# conn_board_v1.net
KiCad netlist of a schematic drawn in EAGLE
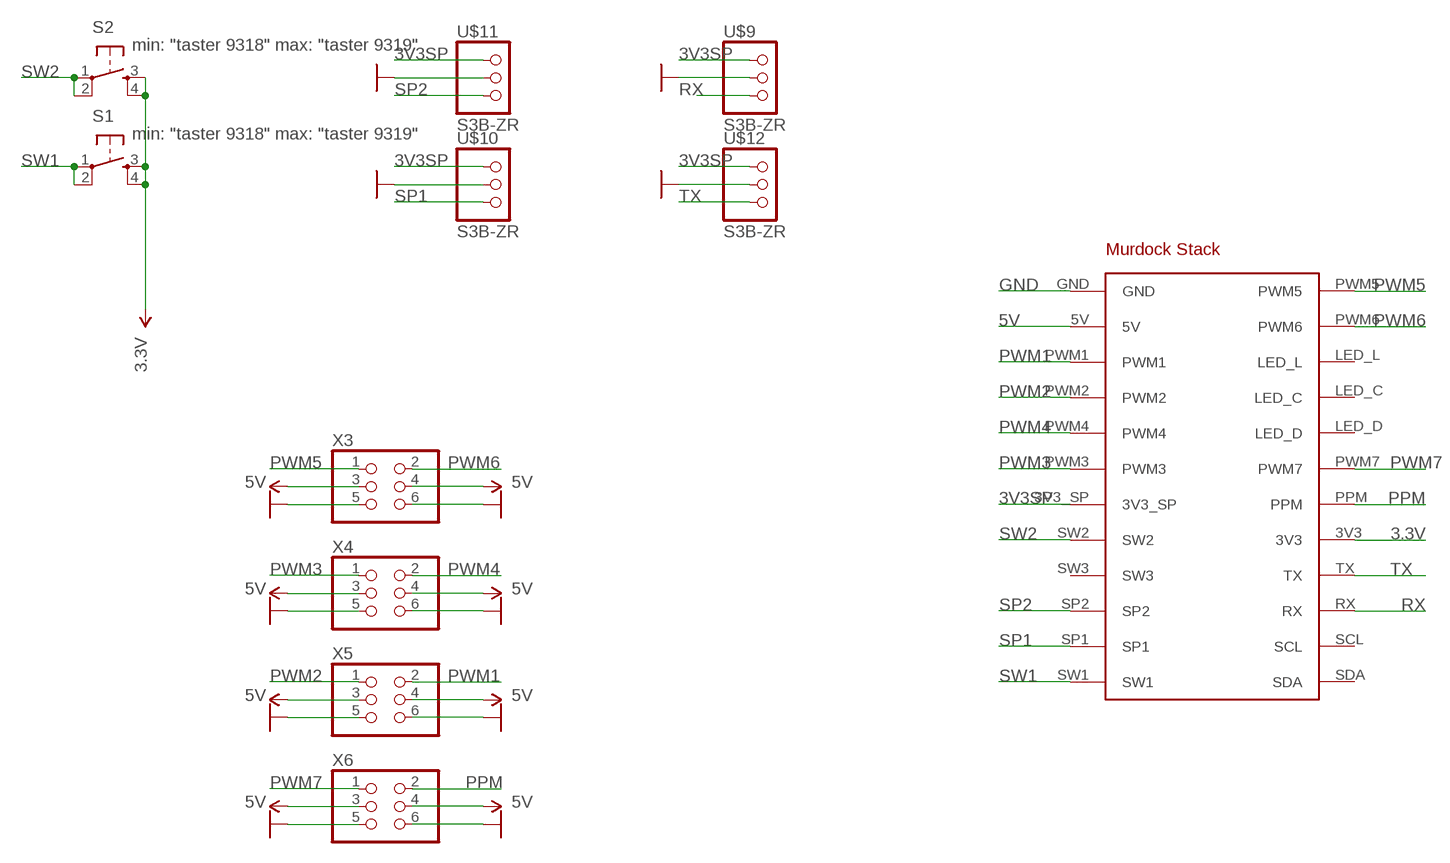
[diagram p0: schematic, sheet 1]

(export (version "E")
  (design (tool "Eeschema 10.0.6"))
  (components
    (comp (ref "S1")
      (value "min: \"taster 9318\" max: \"taster 9319\"")
      (footprint "eagle-import:LSH")
      (libsource (lib "eagle-import") (part "LSH"))
    )
    (comp (ref "S2")
      (value "min: \"taster 9318\" max: \"taster 9319\"")
      (footprint "eagle-import:LSH")
      (libsource (lib "eagle-import") (part "LSH"))
    )
    (comp (ref "U$9")
      (value "S3B-ZR")
      (footprint "eagle-import:S3B-ZR")
      (libsource (lib "eagle-import") (part "S3B-ZR"))
    )
    (comp (ref "U$10")
      (value "S3B-ZR")
      (footprint "eagle-import:S3B-ZR")
      (libsource (lib "eagle-import") (part "S3B-ZR"))
    )
    (comp (ref "U$11")
      (value "S3B-ZR")
      (footprint "eagle-import:S3B-ZR")
      (libsource (lib "eagle-import") (part "S3B-ZR"))
    )
    (comp (ref "U$12")
      (value "S3B-ZR")
      (footprint "eagle-import:S3B-ZR")
      (libsource (lib "eagle-import") (part "S3B-ZR"))
    )
    (comp (ref "X3")
      (value "PINHD-2X3/90")
      (footprint "eagle-import:2X03_90")
      (libsource (lib "eagle-import") (part "PINHD-2X3/90"))
    )
    (comp (ref "X4")
      (value "PINHD-2X3/90")
      (footprint "eagle-import:2X03_90")
      (libsource (lib "eagle-import") (part "PINHD-2X3/90"))
    )
    (comp (ref "X5")
      (value "PINHD-2X3/90")
      (footprint "eagle-import:2X03_90")
      (libsource (lib "eagle-import") (part "PINHD-2X3/90"))
    )
    (comp (ref "X6")
      (value "PINHD-2X3/90")
      (footprint "eagle-import:2X03_90")
      (libsource (lib "eagle-import") (part "PINHD-2X3/90"))
    )
    (comp (ref "X7")
      (value "MURDOCK_STACK")
      (footprint "eagle-import:MURDOCK_STACK")
      (libsource (lib "eagle-import") (part "MURDOCK_STACK"))
    )
  )
  (nets
    (net (code "1") (name "/3V3SP") (class "Default")
      (node (ref "U$10") (pin "1") (pinfunction "1_1") (pintype "bidirectional"))
      (node (ref "U$11") (pin "1") (pinfunction "1_1") (pintype "bidirectional"))
      (node (ref "U$12") (pin "1") (pinfunction "1_1") (pintype "bidirectional"))
      (node (ref "U$9") (pin "1") (pinfunction "1_1") (pintype "bidirectional"))
      (node (ref "X7") (pin "3V3_SP") (pinfunction "3V3_SP_3V3_SP") (pintype "bidirectional"))
    )
    (net (code "2") (name "/PPM") (class "Default")
      (node (ref "X6") (pin "2") (pinfunction "2_2") (pintype "passive"))
      (node (ref "X7") (pin "PPM") (pinfunction "PPM_PPM") (pintype "bidirectional"))
    )
    (net (code "3") (name "/PWM1") (class "Default")
      (node (ref "X5") (pin "2") (pinfunction "2_2") (pintype "passive"))
      (node (ref "X7") (pin "PWM1") (pinfunction "PWM1_PWM1") (pintype "bidirectional"))
    )
    (net (code "4") (name "/PWM2") (class "Default")
      (node (ref "X5") (pin "1") (pinfunction "1_1") (pintype "passive"))
      (node (ref "X7") (pin "PWM2") (pinfunction "PWM2_PWM2") (pintype "bidirectional"))
    )
    (net (code "5") (name "/PWM3") (class "Default")
      (node (ref "X4") (pin "1") (pinfunction "1_1") (pintype "passive"))
      (node (ref "X7") (pin "PWM3") (pinfunction "PWM3_PWM3") (pintype "bidirectional"))
    )
    (net (code "6") (name "/PWM4") (class "Default")
      (node (ref "X4") (pin "2") (pinfunction "2_2") (pintype "passive"))
      (node (ref "X7") (pin "PWM4") (pinfunction "PWM4_PWM4") (pintype "bidirectional"))
    )
    (net (code "7") (name "/PWM5") (class "Default")
      (node (ref "X3") (pin "1") (pinfunction "1_1") (pintype "passive"))
      (node (ref "X7") (pin "PWM5") (pinfunction "PWM5_PWM5") (pintype "bidirectional"))
    )
    (net (code "8") (name "/PWM6") (class "Default")
      (node (ref "X3") (pin "2") (pinfunction "2_2") (pintype "passive"))
      (node (ref "X7") (pin "PWM6") (pinfunction "PWM6_PWM6") (pintype "bidirectional"))
    )
    (net (code "9") (name "/PWM7") (class "Default")
      (node (ref "X6") (pin "1") (pinfunction "1_1") (pintype "passive"))
      (node (ref "X7") (pin "PWM7") (pinfunction "PWM7_PWM7") (pintype "bidirectional"))
    )
    (net (code "10") (name "/RX") (class "Default")
      (node (ref "U$9") (pin "3") (pinfunction "3_3") (pintype "bidirectional"))
      (node (ref "X7") (pin "RX") (pinfunction "RX_RX") (pintype "bidirectional"))
    )
    (net (code "11") (name "/SP1") (class "Default")
      (node (ref "U$10") (pin "3") (pinfunction "3_3") (pintype "bidirectional"))
      (node (ref "X7") (pin "SP1") (pinfunction "SP1_SP1") (pintype "bidirectional"))
    )
    (net (code "12") (name "/SP2") (class "Default")
      (node (ref "U$11") (pin "3") (pinfunction "3_3") (pintype "bidirectional"))
      (node (ref "X7") (pin "SP2") (pinfunction "SP2_SP2") (pintype "bidirectional"))
    )
    (net (code "13") (name "/SW1") (class "Default")
      (node (ref "S1") (pin "1") (pinfunction "1_1") (pintype "passive"))
      (node (ref "S1") (pin "2") (pinfunction "2_2") (pintype "passive"))
      (node (ref "X7") (pin "SW1") (pinfunction "SW1_SW1") (pintype "bidirectional"))
    )
    (net (code "14") (name "/SW2") (class "Default")
      (node (ref "S2") (pin "1") (pinfunction "1_1") (pintype "passive"))
      (node (ref "S2") (pin "2") (pinfunction "2_2") (pintype "passive"))
      (node (ref "X7") (pin "SW2") (pinfunction "SW2_SW2") (pintype "bidirectional"))
    )
    (net (code "15") (name "/TX") (class "Default")
      (node (ref "U$12") (pin "3") (pinfunction "3_3") (pintype "bidirectional"))
      (node (ref "X7") (pin "TX") (pinfunction "TX_TX") (pintype "bidirectional"))
    )
    (net (code "16") (name "3.3V") (class "Default")
      (node (ref "S1") (pin "3") (pinfunction "3_3") (pintype "passive"))
      (node (ref "S1") (pin "4") (pinfunction "4_4") (pintype "passive"))
      (node (ref "S2") (pin "3") (pinfunction "3_3") (pintype "passive"))
      (node (ref "S2") (pin "4") (pinfunction "4_4") (pintype "passive"))
      (node (ref "X7") (pin "3V3") (pinfunction "3V3_3V3") (pintype "bidirectional"))
    )
    (net (code "17") (name "5V") (class "Default")
      (node (ref "X3") (pin "3") (pinfunction "3_3") (pintype "passive"))
      (node (ref "X3") (pin "4") (pinfunction "4_4") (pintype "passive"))
      (node (ref "X4") (pin "3") (pinfunction "3_3") (pintype "passive"))
      (node (ref "X4") (pin "4") (pinfunction "4_4") (pintype "passive"))
      (node (ref "X5") (pin "3") (pinfunction "3_3") (pintype "passive"))
      (node (ref "X5") (pin "4") (pinfunction "4_4") (pintype "passive"))
      (node (ref "X6") (pin "3") (pinfunction "3_3") (pintype "passive"))
      (node (ref "X6") (pin "4") (pinfunction "4_4") (pintype "passive"))
      (node (ref "X7") (pin "5V") (pinfunction "5V_5V") (pintype "bidirectional"))
    )
    (net (code "18") (name "GND") (class "Default")
      (node (ref "U$10") (pin "2") (pinfunction "2_2") (pintype "bidirectional"))
      (node (ref "U$11") (pin "2") (pinfunction "2_2") (pintype "bidirectional"))
      (node (ref "U$12") (pin "2") (pinfunction "2_2") (pintype "bidirectional"))
      (node (ref "U$9") (pin "2") (pinfunction "2_2") (pintype "bidirectional"))
      (node (ref "X3") (pin "5") (pinfunction "5_5") (pintype "passive"))
      (node (ref "X3") (pin "6") (pinfunction "6_6") (pintype "passive"))
      (node (ref "X4") (pin "5") (pinfunction "5_5") (pintype "passive"))
      (node (ref "X4") (pin "6") (pinfunction "6_6") (pintype "passive"))
      (node (ref "X5") (pin "5") (pinfunction "5_5") (pintype "passive"))
      (node (ref "X5") (pin "6") (pinfunction "6_6") (pintype "passive"))
      (node (ref "X6") (pin "5") (pinfunction "5_5") (pintype "passive"))
      (node (ref "X6") (pin "6") (pinfunction "6_6") (pintype "passive"))
      (node (ref "X7") (pin "GND") (pinfunction "GND_GND") (pintype "bidirectional"))
    )
    (net (code "19") (name "unconnected-(X7-PadLED_C)") (class "Default")
      (node (ref "X7") (pin "LED_C") (pinfunction "LED_C_LED_C") (pintype "bidirectional"))
    )
    (net (code "20") (name "unconnected-(X7-PadLED_D)") (class "Default")
      (node (ref "X7") (pin "LED_D") (pinfunction "LED_D_LED_D") (pintype "bidirectional"))
    )
    (net (code "21") (name "unconnected-(X7-PadLED_L)") (class "Default")
      (node (ref "X7") (pin "LED_L") (pinfunction "LED_L_LED_L") (pintype "bidirectional"))
    )
    (net (code "22") (name "unconnected-(X7-PadSCL)") (class "Default")
      (node (ref "X7") (pin "SCL") (pinfunction "SCL_SCL") (pintype "bidirectional"))
    )
    (net (code "23") (name "unconnected-(X7-PadSDA)") (class "Default")
      (node (ref "X7") (pin "SDA") (pinfunction "SDA_SDA") (pintype "bidirectional"))
    )
    (net (code "24") (name "unconnected-(X7-PadSW3)") (class "Default")
      (node (ref "X7") (pin "SW3") (pinfunction "SW3_SW3") (pintype "bidirectional"))
    )
  )
)
